# ArduinoBT.net
KiCad netlist of a schematic drawn in EAGLE
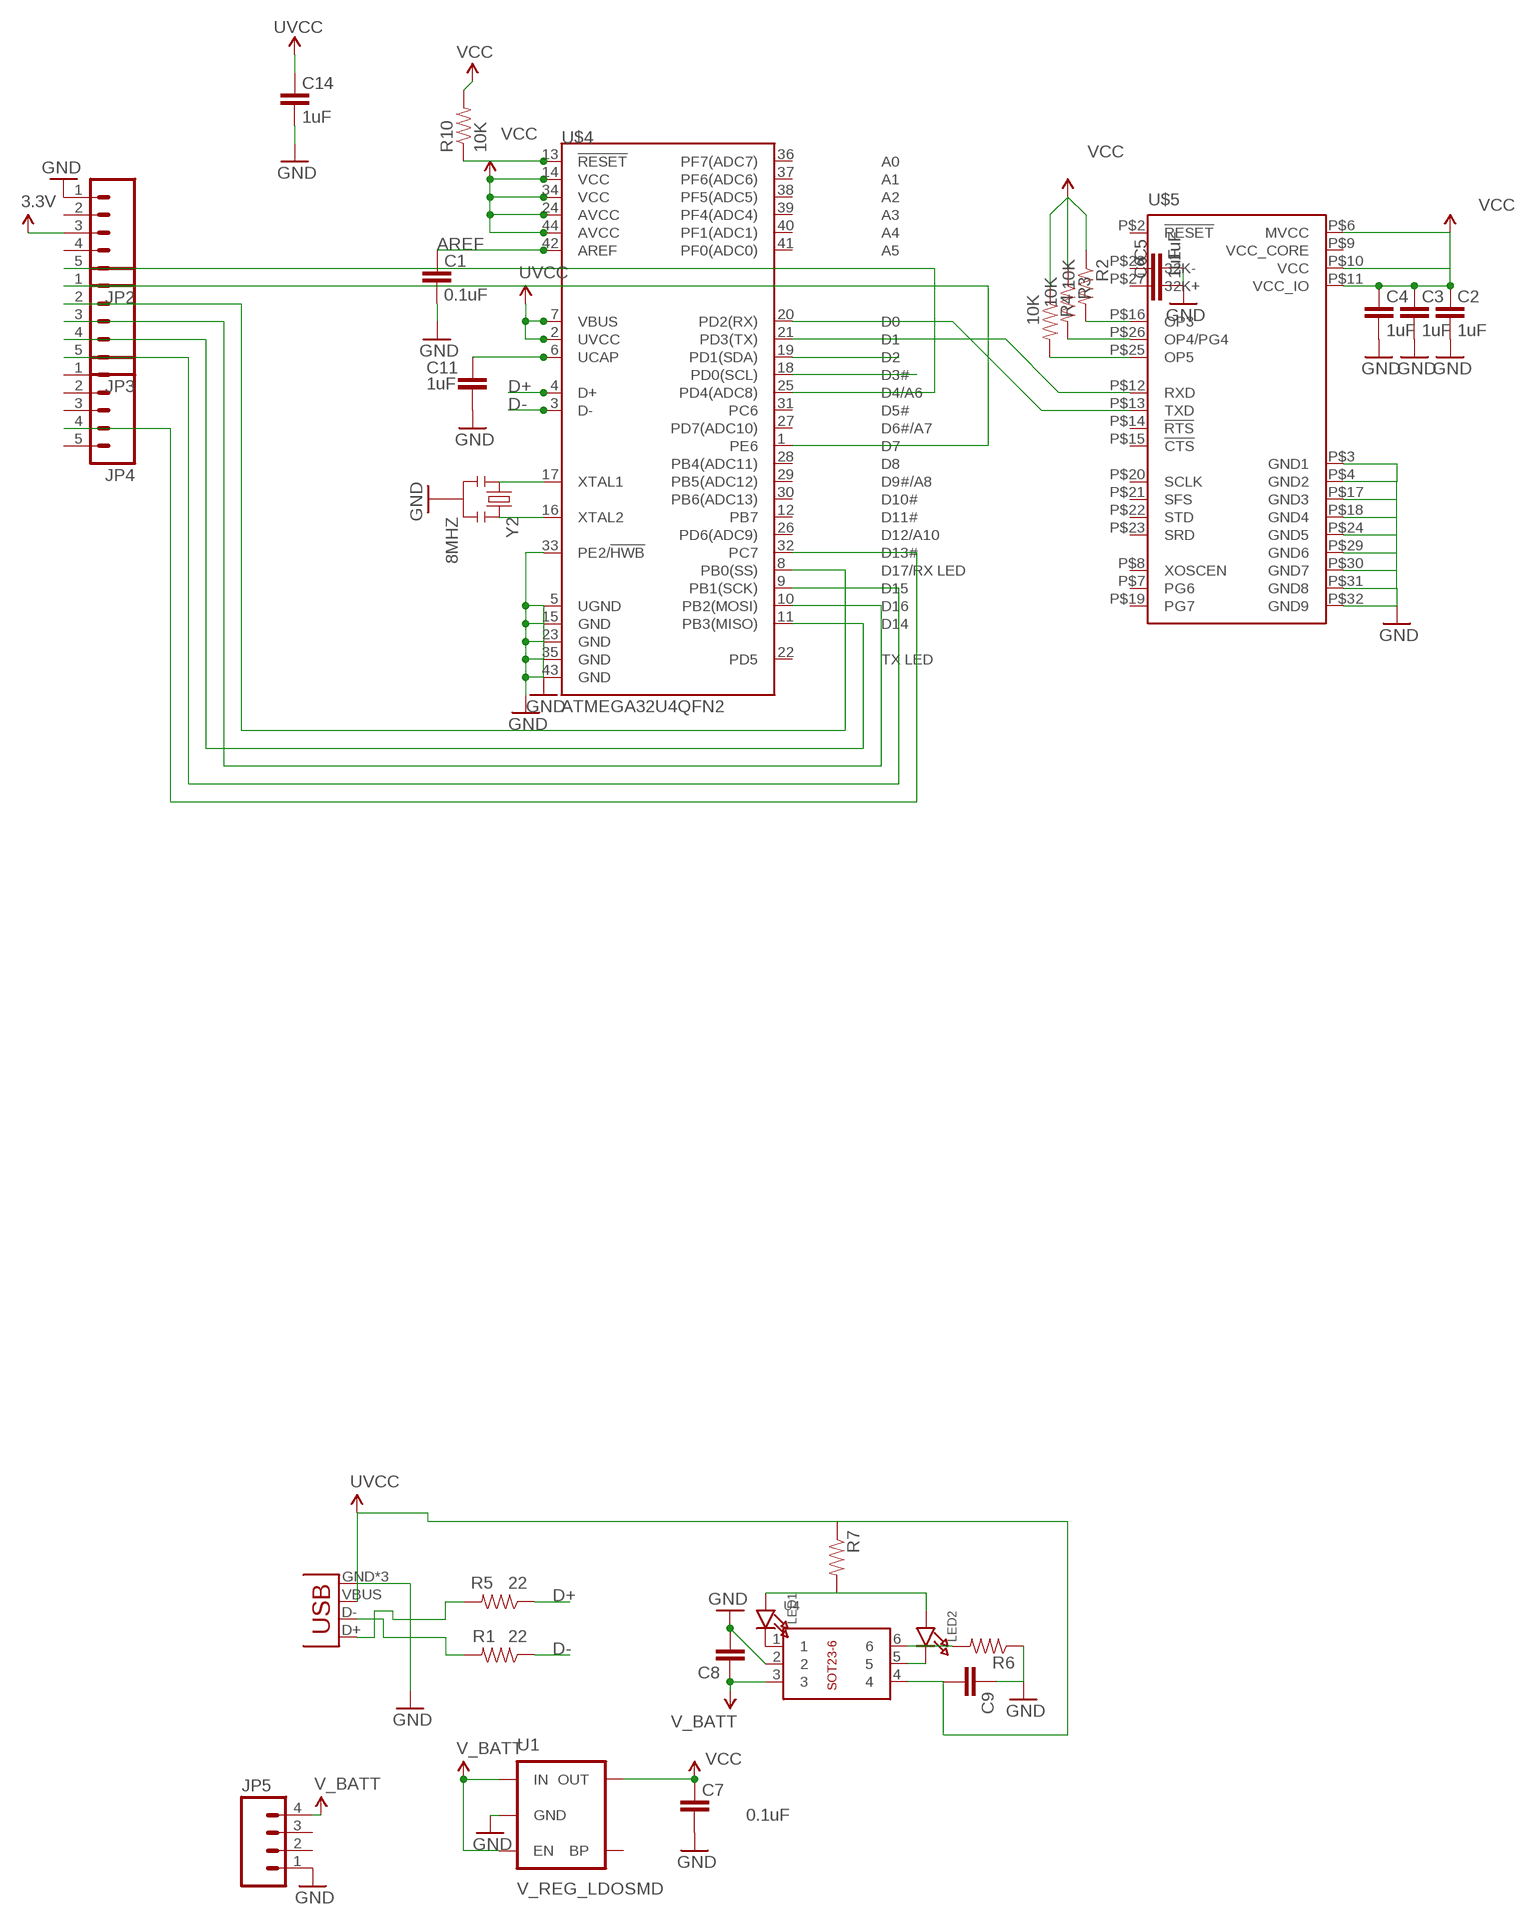
[diagram p0: schematic, sheet 1]

(export (version "E")
  (design (tool "Eeschema 10.0.6"))
  (components
    (comp (ref "C1")
      (value "0.1uF")
      (footprint "eagle-import:0603-CAP")
      (libsource (lib "eagle-import") (part "CAP0603-CAP"))
    )
    (comp (ref "C2")
      (value "1uF")
      (footprint "eagle-import:0603-CAP")
      (libsource (lib "eagle-import") (part "CAP0603-CAP"))
    )
    (comp (ref "C3")
      (value "1uF")
      (footprint "eagle-import:0603-CAP")
      (libsource (lib "eagle-import") (part "CAP0603-CAP"))
    )
    (comp (ref "C4")
      (value "1uF")
      (footprint "eagle-import:0603-CAP")
      (libsource (lib "eagle-import") (part "CAP0603-CAP"))
    )
    (comp (ref "C5")
      (value "1uF")
      (footprint "eagle-import:0603-CAP")
      (libsource (lib "eagle-import") (part "CAP0603-CAP"))
    )
    (comp (ref "C6")
      (value "1uF")
      (footprint "eagle-import:0603-CAP")
      (libsource (lib "eagle-import") (part "CAP0603-CAP"))
    )
    (comp (ref "C7")
      (value "0.1uF")
      (footprint "eagle-import:0603-CAP")
      (libsource (lib "eagle-import") (part "CAP0603-CAP"))
    )
    (comp (ref "C8")
      (value "CAP0805")
      (footprint "eagle-import:0805")
      (libsource (lib "eagle-import") (part "SparkFun-Capacitors_CAP0805"))
    )
    (comp (ref "C9")
      (value "CAP0805")
      (footprint "eagle-import:0805")
      (libsource (lib "eagle-import") (part "SparkFun-Capacitors_CAP0805"))
    )
    (comp (ref "C11")
      (value "1uF")
      (footprint "eagle-import:0603-CAP")
      (libsource (lib "eagle-import") (part "CAP0603-CAP"))
    )
    (comp (ref "C14")
      (value "1uF")
      (footprint "eagle-import:0603-CAP")
      (libsource (lib "eagle-import") (part "CAP0603-CAP"))
    )
    (comp (ref "JP1")
      (value "USB-MICROB")
      (footprint "eagle-import:USB-MICROB")
      (libsource (lib "eagle-import") (part "USB-MICROB"))
    )
    (comp (ref "JP2")
      (value "M051.27MM")
      (footprint "eagle-import:1X05-1.27MM")
      (libsource (lib "eagle-import") (part "M051.27MM"))
    )
    (comp (ref "JP3")
      (value "M051.27MM")
      (footprint "eagle-import:1X05-1.27MM")
      (libsource (lib "eagle-import") (part "M051.27MM"))
    )
    (comp (ref "JP4")
      (value "M051.27MM")
      (footprint "eagle-import:1X05-1.27MM")
      (libsource (lib "eagle-import") (part "M051.27MM"))
    )
    (comp (ref "JP5")
      (value "M041.27MM")
      (footprint "eagle-import:1X04-1.27MM")
      (libsource (lib "eagle-import") (part "M041.27MM"))
    )
    (comp (ref "LED1")
      (value "LED0603_NOOUTLINE")
      (footprint "eagle-import:CHIPLED_0603_NOOUTLINE")
      (libsource (lib "eagle-import") (part "LED0603_NOOUTLINE"))
    )
    (comp (ref "LED2")
      (value "LED0603_NOOUTLINE")
      (footprint "eagle-import:CHIPLED_0603_NOOUTLINE")
      (libsource (lib "eagle-import") (part "LED0603_NOOUTLINE"))
    )
    (comp (ref "R1")
      (value "22")
      (footprint "eagle-import:0603-RES")
      (libsource (lib "eagle-import") (part "RESISTOR0603-RES"))
    )
    (comp (ref "R2")
      (value "10K")
      (footprint "eagle-import:0603-RES")
      (libsource (lib "eagle-import") (part "RESISTOR0603-RES"))
    )
    (comp (ref "R3")
      (value "10K")
      (footprint "eagle-import:0603-RES")
      (libsource (lib "eagle-import") (part "RESISTOR0603-RES"))
    )
    (comp (ref "R4")
      (value "10K")
      (footprint "eagle-import:0603-RES")
      (libsource (lib "eagle-import") (part "RESISTOR0603-RES"))
    )
    (comp (ref "R5")
      (value "22")
      (footprint "eagle-import:0603-RES")
      (libsource (lib "eagle-import") (part "RESISTOR0603-RES"))
    )
    (comp (ref "R6")
      (value "RESISTOR0805-RES")
      (footprint "eagle-import:0805")
      (libsource (lib "eagle-import") (part "SparkFun-Resistors_RESISTOR0805-RES"))
    )
    (comp (ref "R7")
      (value "RESISTOR0805-RES")
      (footprint "eagle-import:0805")
      (libsource (lib "eagle-import") (part "SparkFun-Resistors_RESISTOR0805-RES"))
    )
    (comp (ref "R10")
      (value "10K")
      (footprint "eagle-import:0603-RES")
      (libsource (lib "eagle-import") (part "RESISTOR0603-RES"))
    )
    (comp (ref "U$4")
      (value "ATMEGA32U4QFN2")
      (footprint "eagle-import:SPARKFUN-DIGITALIC_QFN-44-NOPAD")
      (libsource (lib "eagle-import") (part "ATMEGA32U4QFN2"))
    )
    (comp (ref "U$5")
      (value "LMX9838")
      (footprint "eagle-import:LTCC70")
      (libsource (lib "eagle-import") (part "LMX9838"))
    )
    (comp (ref "U1")
      (value "V_REG_LDOSMD")
      (footprint "eagle-import:SOT23-5")
      (libsource (lib "eagle-import") (part "V_REG_LDOSMD"))
    )
    (comp (ref "U4")
      (value "BREAKOUT_SOT23-6")
      (footprint "eagle-import:BREAKOUT_SOT23-6")
      (libsource (lib "eagle-import") (part "BREAKOUT_SOT23-6"))
    )
    (comp (ref "Y2")
      (value "8MHZ")
      (footprint "eagle-import:RESONATOR-SMD")
      (libsource (lib "eagle-import") (part "RESONATOR8MHZ"))
    )
  )
  (nets
    (net (code "1") (name "/AREF") (class "Default")
      (node (ref "C1") (pin "2") (pinfunction "2_2") (pintype "passive"))
      (node (ref "U$4") (pin "42") (pinfunction "AREF_42") (pintype "bidirectional"))
    )
    (net (code "2") (name "/D+") (class "Default")
      (node (ref "R5") (pin "1") (pinfunction "1_1") (pintype "passive"))
      (node (ref "U$4") (pin "4") (pinfunction "D+_4") (pintype "bidirectional"))
    )
    (net (code "3") (name "/D-") (class "Default")
      (node (ref "R1") (pin "1") (pinfunction "1_1") (pintype "passive"))
      (node (ref "U$4") (pin "3") (pinfunction "D-_3") (pintype "bidirectional"))
    )
    (net (code "4") (name "/VCC_CORE") (class "Default")
      (node (ref "U$5") (pin "P$9") (pinfunction "VCC_CORE_P$9") (pintype "power_in"))
    )
    (net (code "5") (name "3.3V") (class "Default")
      (node (ref "C2") (pin "2") (pinfunction "2_2") (pintype "passive"))
      (node (ref "C3") (pin "2") (pinfunction "2_2") (pintype "passive"))
      (node (ref "C4") (pin "2") (pinfunction "2_2") (pintype "passive"))
      (node (ref "C7") (pin "2") (pinfunction "2_2") (pintype "passive"))
      (node (ref "JP2") (pin "3") (pinfunction "3_3") (pintype "passive"))
      (node (ref "R10") (pin "2") (pinfunction "2_2") (pintype "passive"))
      (node (ref "R2") (pin "1") (pinfunction "1_1") (pintype "passive"))
      (node (ref "R3") (pin "1") (pinfunction "1_1") (pintype "passive"))
      (node (ref "R4") (pin "1") (pinfunction "1_1") (pintype "passive"))
      (node (ref "U$4") (pin "14") (pinfunction "VCC_14") (pintype "bidirectional"))
      (node (ref "U$4") (pin "24") (pinfunction "AVCC_24") (pintype "bidirectional"))
      (node (ref "U$4") (pin "34") (pinfunction "VCC_34") (pintype "bidirectional"))
      (node (ref "U$4") (pin "44") (pinfunction "AVCC_44") (pintype "bidirectional"))
      (node (ref "U$5") (pin "P$10") (pinfunction "VCC_P$10") (pintype "power_in"))
      (node (ref "U$5") (pin "P$11") (pinfunction "VCC_IO_P$11") (pintype "power_in"))
      (node (ref "U$5") (pin "P$6") (pinfunction "MVCC_P$6") (pintype "power_in"))
      (node (ref "U1") (pin "5") (pinfunction "OUT_5") (pintype "passive"))
    )
    (net (code "6") (name "GND") (class "Default")
      (node (ref "C1") (pin "1") (pinfunction "1_1") (pintype "passive"))
      (node (ref "C11") (pin "1") (pinfunction "1_1") (pintype "passive"))
      (node (ref "C14") (pin "1") (pinfunction "1_1") (pintype "passive"))
      (node (ref "C2") (pin "1") (pinfunction "1_1") (pintype "passive"))
      (node (ref "C3") (pin "1") (pinfunction "1_1") (pintype "passive"))
      (node (ref "C4") (pin "1") (pinfunction "1_1") (pintype "passive"))
      (node (ref "C5") (pin "1") (pinfunction "1_1") (pintype "passive"))
      (node (ref "C6") (pin "1") (pinfunction "1_1") (pintype "passive"))
      (node (ref "C7") (pin "1") (pinfunction "1_1") (pintype "passive"))
      (node (ref "C8") (pin "2") (pinfunction "2_2") (pintype "passive"))
      (node (ref "C9") (pin "1") (pinfunction "1_1") (pintype "passive"))
      (node (ref "JP1") (pin "GND") (pinfunction "GND_GND") (pintype "bidirectional"))
      (node (ref "JP1") (pin "MT1") (pinfunction "GND_MT1") (pintype "bidirectional"))
      (node (ref "JP1") (pin "MT2") (pinfunction "GND_MT2") (pintype "bidirectional"))
      (node (ref "JP2") (pin "1") (pinfunction "1_1") (pintype "passive"))
      (node (ref "JP5") (pin "1") (pinfunction "1_1") (pintype "passive"))
      (node (ref "R6") (pin "1") (pinfunction "1_1") (pintype "passive"))
      (node (ref "U$4") (pin "15") (pinfunction "GND_15") (pintype "bidirectional"))
      (node (ref "U$4") (pin "23") (pinfunction "GND_23") (pintype "bidirectional"))
      (node (ref "U$4") (pin "33") (pinfunction "PE2/~{HWB}_33") (pintype "bidirectional"))
      (node (ref "U$4") (pin "35") (pinfunction "GND_35") (pintype "bidirectional"))
      (node (ref "U$4") (pin "43") (pinfunction "GND_43") (pintype "bidirectional"))
      (node (ref "U$4") (pin "5") (pinfunction "UGND_5") (pintype "bidirectional"))
      (node (ref "U$5") (pin "P$17") (pinfunction "GND3_P$17") (pintype "power_in"))
      (node (ref "U$5") (pin "P$18") (pinfunction "GND4_P$18") (pintype "power_in"))
      (node (ref "U$5") (pin "P$24") (pinfunction "GND5_P$24") (pintype "power_in"))
      (node (ref "U$5") (pin "P$29") (pinfunction "GND6_P$29") (pintype "power_in"))
      (node (ref "U$5") (pin "P$3") (pinfunction "GND1_P$3") (pintype "power_in"))
      (node (ref "U$5") (pin "P$30") (pinfunction "GND7_P$30") (pintype "power_in"))
      (node (ref "U$5") (pin "P$31") (pinfunction "GND8_P$31") (pintype "power_in"))
      (node (ref "U$5") (pin "P$32") (pinfunction "GND9_P$32") (pintype "power_in"))
      (node (ref "U$5") (pin "P$4") (pinfunction "GND2_P$4") (pintype "power_in"))
      (node (ref "U1") (pin "2") (pinfunction "GND_2") (pintype "input"))
      (node (ref "U4") (pin "2") (pinfunction "2_2") (pintype "bidirectional"))
      (node (ref "Y2") (pin "2") (pinfunction "2_2") (pintype "passive"))
    )
    (net (code "7") (name "Net-(JP1-PadD+)") (class "Default")
      (node (ref "JP1") (pin "D+") (pinfunction "D+_D+") (pintype "bidirectional"))
      (node (ref "R5") (pin "2") (pinfunction "2_2") (pintype "passive"))
    )
    (net (code "8") (name "Net-(JP1-PadD-)") (class "Default")
      (node (ref "JP1") (pin "D-") (pinfunction "D-_D-") (pintype "bidirectional"))
      (node (ref "R1") (pin "2") (pinfunction "2_2") (pintype "passive"))
    )
    (net (code "9") (name "Net-(LED1-PadA)") (class "Default")
      (node (ref "LED1") (pin "A") (pinfunction "A_A") (pintype "passive"))
      (node (ref "LED2") (pin "A") (pinfunction "A_A") (pintype "passive"))
      (node (ref "R7") (pin "2") (pinfunction "2_2") (pintype "passive"))
    )
    (net (code "10") (name "Net-(LED1-PadC)") (class "Default")
      (node (ref "LED1") (pin "C") (pinfunction "C_C") (pintype "passive"))
      (node (ref "U4") (pin "1") (pinfunction "1_1") (pintype "bidirectional"))
    )
    (net (code "11") (name "Net-(LED2-PadC)") (class "Default")
      (node (ref "LED2") (pin "C") (pinfunction "C_C") (pintype "passive"))
      (node (ref "U4") (pin "5") (pinfunction "5_5") (pintype "bidirectional"))
    )
    (net (code "12") (name "Net-(R6-Pad2)") (class "Default")
      (node (ref "R6") (pin "2") (pinfunction "2_2") (pintype "passive"))
      (node (ref "U4") (pin "6") (pinfunction "6_6") (pintype "bidirectional"))
    )
    (net (code "13") (name "Net-(U$4-PB0(SS))") (class "Default")
      (node (ref "JP3") (pin "2") (pinfunction "2_2") (pintype "passive"))
      (node (ref "U$4") (pin "8") (pinfunction "PB0(SS)_8") (pintype "bidirectional"))
    )
    (net (code "14") (name "Net-(U$4-PB1(SCK))") (class "Default")
      (node (ref "JP3") (pin "5") (pinfunction "5_5") (pintype "passive"))
      (node (ref "U$4") (pin "9") (pinfunction "PB1(SCK)_9") (pintype "bidirectional"))
    )
    (net (code "15") (name "Net-(U$4-PB2(MOSI))") (class "Default")
      (node (ref "JP3") (pin "3") (pinfunction "3_3") (pintype "passive"))
      (node (ref "U$4") (pin "10") (pinfunction "PB2(MOSI)_10") (pintype "bidirectional"))
    )
    (net (code "16") (name "Net-(U$4-PB3(MISO))") (class "Default")
      (node (ref "JP3") (pin "4") (pinfunction "4_4") (pintype "passive"))
      (node (ref "U$4") (pin "11") (pinfunction "PB3(MISO)_11") (pintype "bidirectional"))
    )
    (net (code "17") (name "Net-(U$4-PC7)") (class "Default")
      (node (ref "JP4") (pin "4") (pinfunction "4_4") (pintype "passive"))
      (node (ref "U$4") (pin "32") (pinfunction "PC7_32") (pintype "bidirectional"))
    )
    (net (code "18") (name "Net-(U$4-PD2(RX))") (class "Default")
      (node (ref "U$4") (pin "20") (pinfunction "PD2(RX)_20") (pintype "bidirectional"))
      (node (ref "U$5") (pin "P$13") (pinfunction "TXD_P$13") (pintype "output"))
    )
    (net (code "19") (name "Net-(U$4-PD3(TX))") (class "Default")
      (node (ref "U$4") (pin "21") (pinfunction "PD3(TX)_21") (pintype "bidirectional"))
      (node (ref "U$5") (pin "P$12") (pinfunction "RXD_P$12") (pintype "input"))
    )
    (net (code "20") (name "Net-(U$4-PD4(ADC8))") (class "Default")
      (node (ref "JP2") (pin "5") (pinfunction "5_5") (pintype "passive"))
      (node (ref "U$4") (pin "25") (pinfunction "PD4(ADC8)_25") (pintype "bidirectional"))
    )
    (net (code "21") (name "Net-(U$4-PE6)") (class "Default")
      (node (ref "JP3") (pin "1") (pinfunction "1_1") (pintype "passive"))
      (node (ref "U$4") (pin "1") (pinfunction "PE6_1") (pintype "bidirectional"))
    )
    (net (code "22") (name "Net-(U$4-UCAP)") (class "Default")
      (node (ref "C11") (pin "2") (pinfunction "2_2") (pintype "passive"))
      (node (ref "U$4") (pin "6") (pinfunction "UCAP_6") (pintype "bidirectional"))
    )
    (net (code "23") (name "Net-(U$4-XTAL1)") (class "Default")
      (node (ref "U$4") (pin "17") (pinfunction "XTAL1_17") (pintype "bidirectional"))
      (node (ref "Y2") (pin "1") (pinfunction "1_1") (pintype "passive"))
    )
    (net (code "24") (name "Net-(U$4-XTAL2)") (class "Default")
      (node (ref "U$4") (pin "16") (pinfunction "XTAL2_16") (pintype "bidirectional"))
      (node (ref "Y2") (pin "3") (pinfunction "3_3") (pintype "passive"))
    )
    (net (code "25") (name "Net-(U$4-~{RESET})") (class "Default")
      (node (ref "R10") (pin "1") (pinfunction "1_1") (pintype "passive"))
      (node (ref "U$4") (pin "13") (pinfunction "~{RESET}_13") (pintype "bidirectional"))
    )
    (net (code "26") (name "Net-(U$5-32K+)") (class "Default")
      (node (ref "C6") (pin "2") (pinfunction "2_2") (pintype "passive"))
      (node (ref "U$5") (pin "P$27") (pinfunction "32K+_P$27") (pintype "input"))
    )
    (net (code "27") (name "Net-(U$5-32K-)") (class "Default")
      (node (ref "C5") (pin "2") (pinfunction "2_2") (pintype "passive"))
      (node (ref "U$5") (pin "P$28") (pinfunction "32K-_P$28") (pintype "output"))
    )
    (net (code "28") (name "Net-(U$5-OP3)") (class "Default")
      (node (ref "R2") (pin "2") (pinfunction "2_2") (pintype "passive"))
      (node (ref "U$5") (pin "P$16") (pinfunction "OP3_P$16") (pintype "input"))
    )
    (net (code "29") (name "Net-(U$5-OP4{slash}PG4)") (class "Default")
      (node (ref "R3") (pin "2") (pinfunction "2_2") (pintype "passive"))
      (node (ref "U$5") (pin "P$26") (pinfunction "OP4/PG4_P$26") (pintype "bidirectional"))
    )
    (net (code "30") (name "Net-(U$5-OP5)") (class "Default")
      (node (ref "R4") (pin "2") (pinfunction "2_2") (pintype "passive"))
      (node (ref "U$5") (pin "P$25") (pinfunction "OP5_P$25") (pintype "bidirectional"))
    )
    (net (code "31") (name "UVCC") (class "Default")
      (node (ref "C14") (pin "2") (pinfunction "2_2") (pintype "passive"))
      (node (ref "C9") (pin "2") (pinfunction "2_2") (pintype "passive"))
      (node (ref "JP1") (pin "VBUS") (pinfunction "VBUS_VBUS") (pintype "bidirectional"))
      (node (ref "R7") (pin "1") (pinfunction "1_1") (pintype "passive"))
      (node (ref "U$4") (pin "2") (pinfunction "UVCC_2") (pintype "bidirectional"))
      (node (ref "U$4") (pin "7") (pinfunction "VBUS_7") (pintype "bidirectional"))
      (node (ref "U4") (pin "4") (pinfunction "4_4") (pintype "bidirectional"))
    )
    (net (code "32") (name "V_BATT") (class "Default")
      (node (ref "C8") (pin "1") (pinfunction "1_1") (pintype "passive"))
      (node (ref "JP5") (pin "4") (pinfunction "4_4") (pintype "passive"))
      (node (ref "U1") (pin "1") (pinfunction "IN_1") (pintype "input"))
      (node (ref "U1") (pin "3") (pinfunction "EN_3") (pintype "input"))
      (node (ref "U4") (pin "3") (pinfunction "3_3") (pintype "bidirectional"))
    )
    (net (code "33") (name "unconnected-(JP2-Pad2)") (class "Default")
      (node (ref "JP2") (pin "2") (pinfunction "2_2") (pintype "passive"))
    )
    (net (code "34") (name "unconnected-(JP2-Pad4)") (class "Default")
      (node (ref "JP2") (pin "4") (pinfunction "4_4") (pintype "passive"))
    )
    (net (code "35") (name "unconnected-(JP4-Pad1)") (class "Default")
      (node (ref "JP4") (pin "1") (pinfunction "1_1") (pintype "passive"))
    )
    (net (code "36") (name "unconnected-(JP4-Pad2)") (class "Default")
      (node (ref "JP4") (pin "2") (pinfunction "2_2") (pintype "passive"))
    )
    (net (code "37") (name "unconnected-(JP4-Pad3)") (class "Default")
      (node (ref "JP4") (pin "3") (pinfunction "3_3") (pintype "passive"))
    )
    (net (code "38") (name "unconnected-(JP4-Pad5)") (class "Default")
      (node (ref "JP4") (pin "5") (pinfunction "5_5") (pintype "passive"))
    )
    (net (code "39") (name "unconnected-(JP5-Pad2)") (class "Default")
      (node (ref "JP5") (pin "2") (pinfunction "2_2") (pintype "passive"))
    )
    (net (code "40") (name "unconnected-(JP5-Pad3)") (class "Default")
      (node (ref "JP5") (pin "3") (pinfunction "3_3") (pintype "passive"))
    )
    (net (code "41") (name "unconnected-(U$4-PB4(ADC11)-Pad28)") (class "Default")
      (node (ref "U$4") (pin "28") (pinfunction "PB4(ADC11)_28") (pintype "bidirectional"))
    )
    (net (code "42") (name "unconnected-(U$4-PB5(ADC12)-Pad29)") (class "Default")
      (node (ref "U$4") (pin "29") (pinfunction "PB5(ADC12)_29") (pintype "bidirectional"))
    )
    (net (code "43") (name "unconnected-(U$4-PB6(ADC13)-Pad30)") (class "Default")
      (node (ref "U$4") (pin "30") (pinfunction "PB6(ADC13)_30") (pintype "bidirectional"))
    )
    (net (code "44") (name "unconnected-(U$4-PB7-Pad12)") (class "Default")
      (node (ref "U$4") (pin "12") (pinfunction "PB7_12") (pintype "bidirectional"))
    )
    (net (code "45") (name "unconnected-(U$4-PC6-Pad31)") (class "Default")
      (node (ref "U$4") (pin "31") (pinfunction "PC6_31") (pintype "bidirectional"))
    )
    (net (code "46") (name "unconnected-(U$4-PD0(SCL)-Pad18)") (class "Default")
      (node (ref "U$4") (pin "18") (pinfunction "PD0(SCL)_18") (pintype "bidirectional"))
    )
    (net (code "47") (name "unconnected-(U$4-PD1(SDA)-Pad19)") (class "Default")
      (node (ref "U$4") (pin "19") (pinfunction "PD1(SDA)_19") (pintype "bidirectional"))
    )
    (net (code "48") (name "unconnected-(U$4-PD5-Pad22)") (class "Default")
      (node (ref "U$4") (pin "22") (pinfunction "PD5_22") (pintype "bidirectional"))
    )
    (net (code "49") (name "unconnected-(U$4-PD6(ADC9)-Pad26)") (class "Default")
      (node (ref "U$4") (pin "26") (pinfunction "PD6(ADC9)_26") (pintype "bidirectional"))
    )
    (net (code "50") (name "unconnected-(U$4-PD7(ADC10)-Pad27)") (class "Default")
      (node (ref "U$4") (pin "27") (pinfunction "PD7(ADC10)_27") (pintype "bidirectional"))
    )
    (net (code "51") (name "unconnected-(U$4-PF0(ADC0)-Pad41)") (class "Default")
      (node (ref "U$4") (pin "41") (pinfunction "PF0(ADC0)_41") (pintype "bidirectional"))
    )
    (net (code "52") (name "unconnected-(U$4-PF1(ADC1)-Pad40)") (class "Default")
      (node (ref "U$4") (pin "40") (pinfunction "PF1(ADC1)_40") (pintype "bidirectional"))
    )
    (net (code "53") (name "unconnected-(U$4-PF4(ADC4)-Pad39)") (class "Default")
      (node (ref "U$4") (pin "39") (pinfunction "PF4(ADC4)_39") (pintype "bidirectional"))
    )
    (net (code "54") (name "unconnected-(U$4-PF5(ADC5)-Pad38)") (class "Default")
      (node (ref "U$4") (pin "38") (pinfunction "PF5(ADC5)_38") (pintype "bidirectional"))
    )
    (net (code "55") (name "unconnected-(U$4-PF6(ADC6)-Pad37)") (class "Default")
      (node (ref "U$4") (pin "37") (pinfunction "PF6(ADC6)_37") (pintype "bidirectional"))
    )
    (net (code "56") (name "unconnected-(U$4-PF7(ADC7)-Pad36)") (class "Default")
      (node (ref "U$4") (pin "36") (pinfunction "PF7(ADC7)_36") (pintype "bidirectional"))
    )
    (net (code "57") (name "unconnected-(U$5-PG6-PadP$7)") (class "Default")
      (node (ref "U$5") (pin "P$7") (pinfunction "PG6_P$7") (pintype "bidirectional"))
    )
    (net (code "58") (name "unconnected-(U$5-PG7-PadP$19)") (class "Default")
      (node (ref "U$5") (pin "P$19") (pinfunction "PG7_P$19") (pintype "bidirectional"))
    )
    (net (code "59") (name "unconnected-(U$5-SCLK-PadP$20)") (class "Default")
      (node (ref "U$5") (pin "P$20") (pinfunction "SCLK_P$20") (pintype "bidirectional"))
    )
    (net (code "60") (name "unconnected-(U$5-SFS-PadP$21)") (class "Default")
      (node (ref "U$5") (pin "P$21") (pinfunction "SFS_P$21") (pintype "bidirectional"))
    )
    (net (code "61") (name "unconnected-(U$5-SRD-PadP$23)") (class "Default")
      (node (ref "U$5") (pin "P$23") (pinfunction "SRD_P$23") (pintype "input"))
    )
    (net (code "62") (name "unconnected-(U$5-STD-PadP$22)") (class "Default")
      (node (ref "U$5") (pin "P$22") (pinfunction "STD_P$22") (pintype "output"))
    )
    (net (code "63") (name "unconnected-(U$5-XOSCEN-PadP$8)") (class "Default")
      (node (ref "U$5") (pin "P$8") (pinfunction "XOSCEN_P$8") (pintype "output"))
    )
    (net (code "64") (name "unconnected-(U$5-~{CTS}-PadP$15)") (class "Default")
      (node (ref "U$5") (pin "P$15") (pinfunction "~{CTS}_P$15") (pintype "input"))
    )
    (net (code "65") (name "unconnected-(U$5-~{RESET}-PadP$2)") (class "Default")
      (node (ref "U$5") (pin "P$2") (pinfunction "~{RESET}_P$2") (pintype "input"))
    )
    (net (code "66") (name "unconnected-(U$5-~{RTS}-PadP$14)") (class "Default")
      (node (ref "U$5") (pin "P$14") (pinfunction "~{RTS}_P$14") (pintype "output"))
    )
    (net (code "67") (name "unconnected-(U1-BP-Pad4)") (class "Default")
      (node (ref "U1") (pin "4") (pinfunction "BP_4") (pintype "input"))
    )
  )
)
